# design.net
KiCad netlist of a schematic drawn in Altium Designer
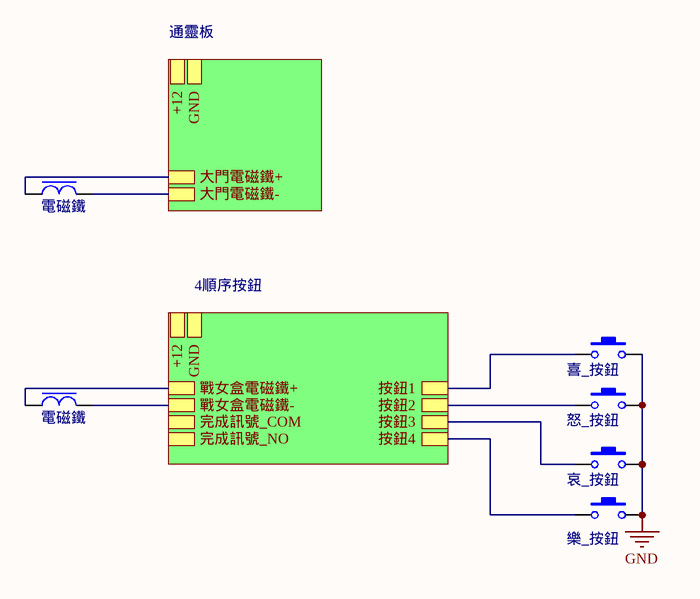
[diagram p0: 松菸_幻影光靈_屍禁.SchDoc]

(export (version "E")
  (design (tool "Eeschema 10.0.6"))
  (components
    (comp (ref "I7")
      (value "電磁鐵")
      (footprint "Inductor-0420")
      (description "一體成型電感")
      (libsource (lib "MyLibray") (part "Inductor"))
    )
    (comp (ref "I9")
      (value "電磁鐵")
      (footprint "Inductor-0420")
      (description "一體成型電感")
      (libsource (lib "MyLibray") (part "Inductor"))
    )
    (comp (ref "S24")
      (value "喜_按鈕")
      (footprint "Switch SMD-3.6*6*2.5")
      (description "開關_按鍵")
      (libsource (lib "MyLibray") (part "Switch"))
    )
    (comp (ref "S25")
      (value "怒_按鈕")
      (footprint "Switch SMD-3.6*6*2.5")
      (description "開關_按鍵")
      (libsource (lib "MyLibray") (part "Switch"))
    )
    (comp (ref "S26")
      (value "哀_按鈕")
      (footprint "Switch SMD-3.6*6*2.5")
      (description "開關_按鍵")
      (libsource (lib "MyLibray") (part "Switch"))
    )
    (comp (ref "S27")
      (value "樂_按鈕")
      (footprint "Switch SMD-3.6*6*2.5")
      (description "開關_按鍵")
      (libsource (lib "MyLibray") (part "Switch"))
    )
  )
  (nets
    (net (code "5") (name "/大門電磁鐵+") (class "Default")
      (node (ref "I7") (pin "2") (pinfunction "2_2") (pintype "passive"))
    )
    (net (code "6") (name "/大門電磁鐵-") (class "Default")
      (node (ref "I7") (pin "1") (pinfunction "1_1") (pintype "passive"))
    )
    (net (code "9") (name "/戰女盒電磁鐵+") (class "Default")
      (node (ref "I9") (pin "2") (pinfunction "2_2") (pintype "passive"))
    )
    (net (code "10") (name "/戰女盒電磁鐵-") (class "Default")
      (node (ref "I9") (pin "1") (pinfunction "1_1") (pintype "passive"))
    )
    (net (code "11") (name "/按鈕1") (class "Default")
      (node (ref "S24") (pin "1") (pinfunction "1_1") (pintype "passive"))
    )
    (net (code "12") (name "/按鈕2") (class "Default")
      (node (ref "S25") (pin "1") (pinfunction "1_1") (pintype "passive"))
    )
    (net (code "13") (name "/按鈕3") (class "Default")
      (node (ref "S26") (pin "1") (pinfunction "1_1") (pintype "passive"))
    )
    (net (code "14") (name "/按鈕4") (class "Default")
      (node (ref "S27") (pin "1") (pinfunction "1_1") (pintype "passive"))
    )
    (net (code "15") (name "GND") (class "Default")
      (node (ref "S24") (pin "2") (pinfunction "2_2") (pintype "passive"))
      (node (ref "S25") (pin "2") (pinfunction "2_2") (pintype "passive"))
      (node (ref "S26") (pin "2") (pinfunction "2_2") (pintype "passive"))
      (node (ref "S27") (pin "2") (pinfunction "2_2") (pintype "passive"))
    )
  )
)
